# myWatch.net
KiCad netlist of a schematic drawn in EAGLE
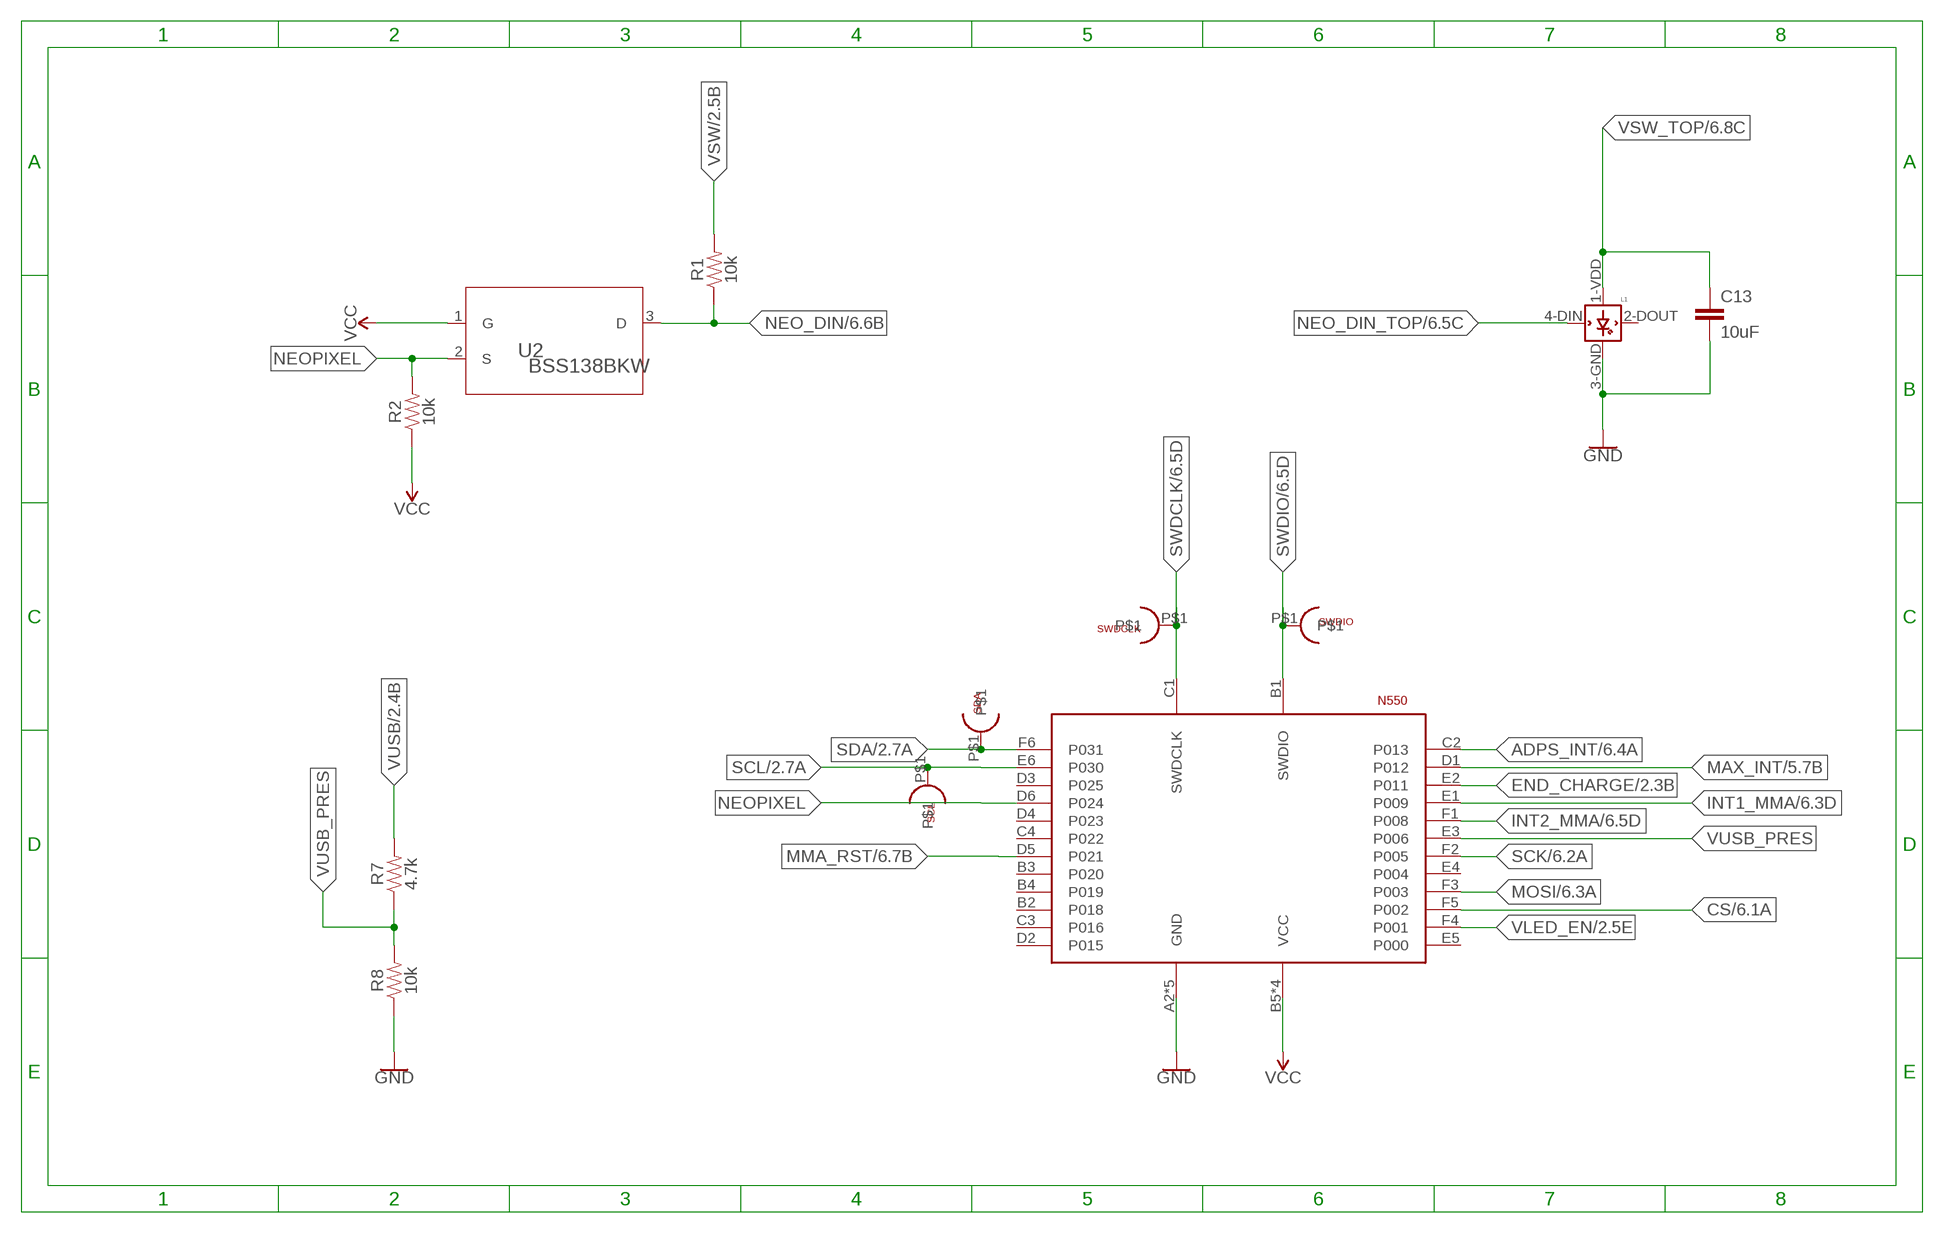
[diagram p0: schematic, sheet 1]
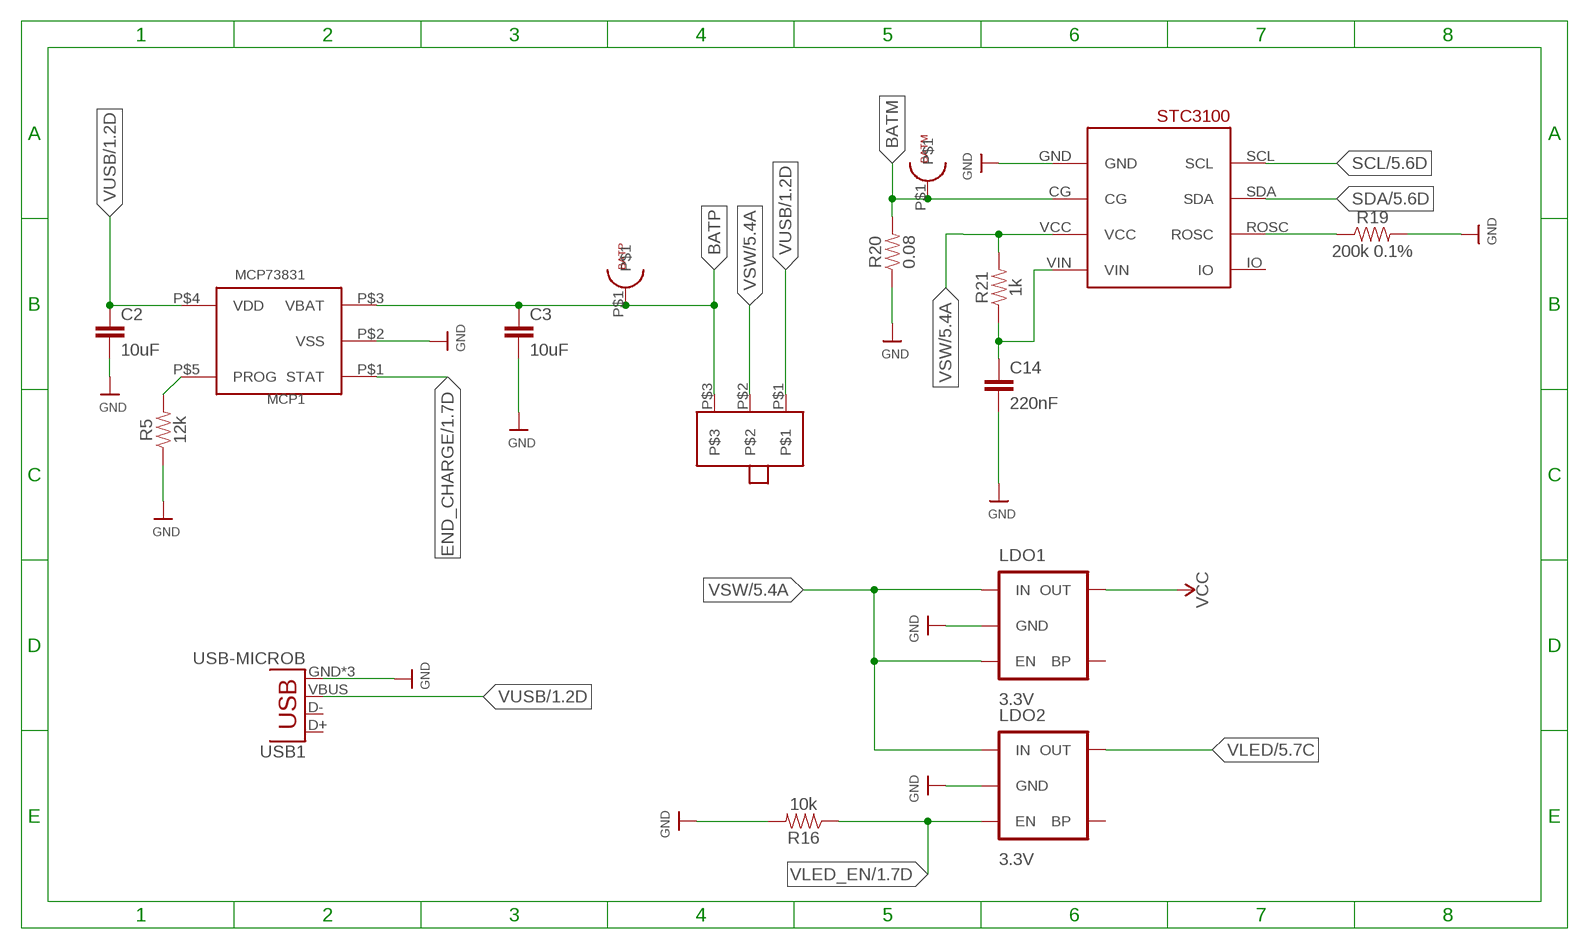
[diagram p1: schematic, sheet 2]
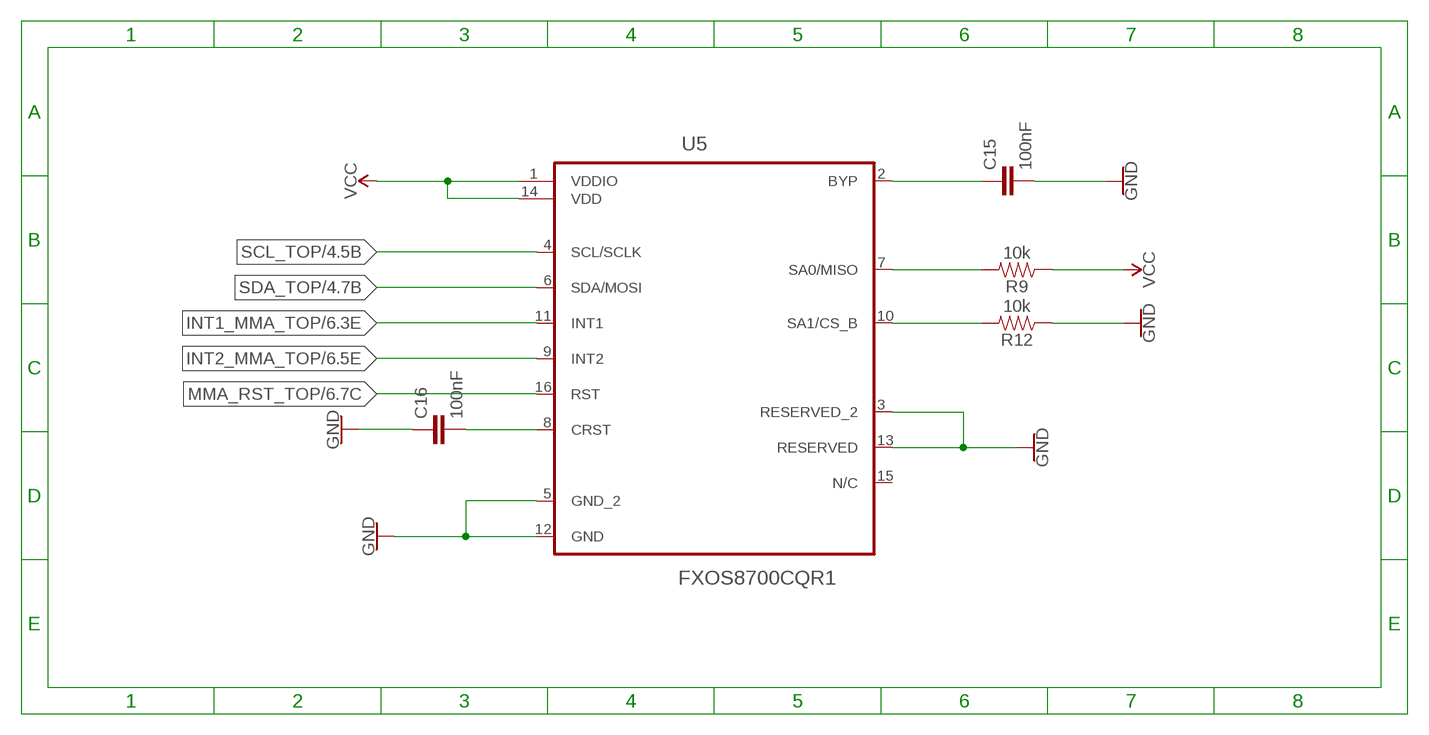
[diagram p2: schematic, sheet 3]
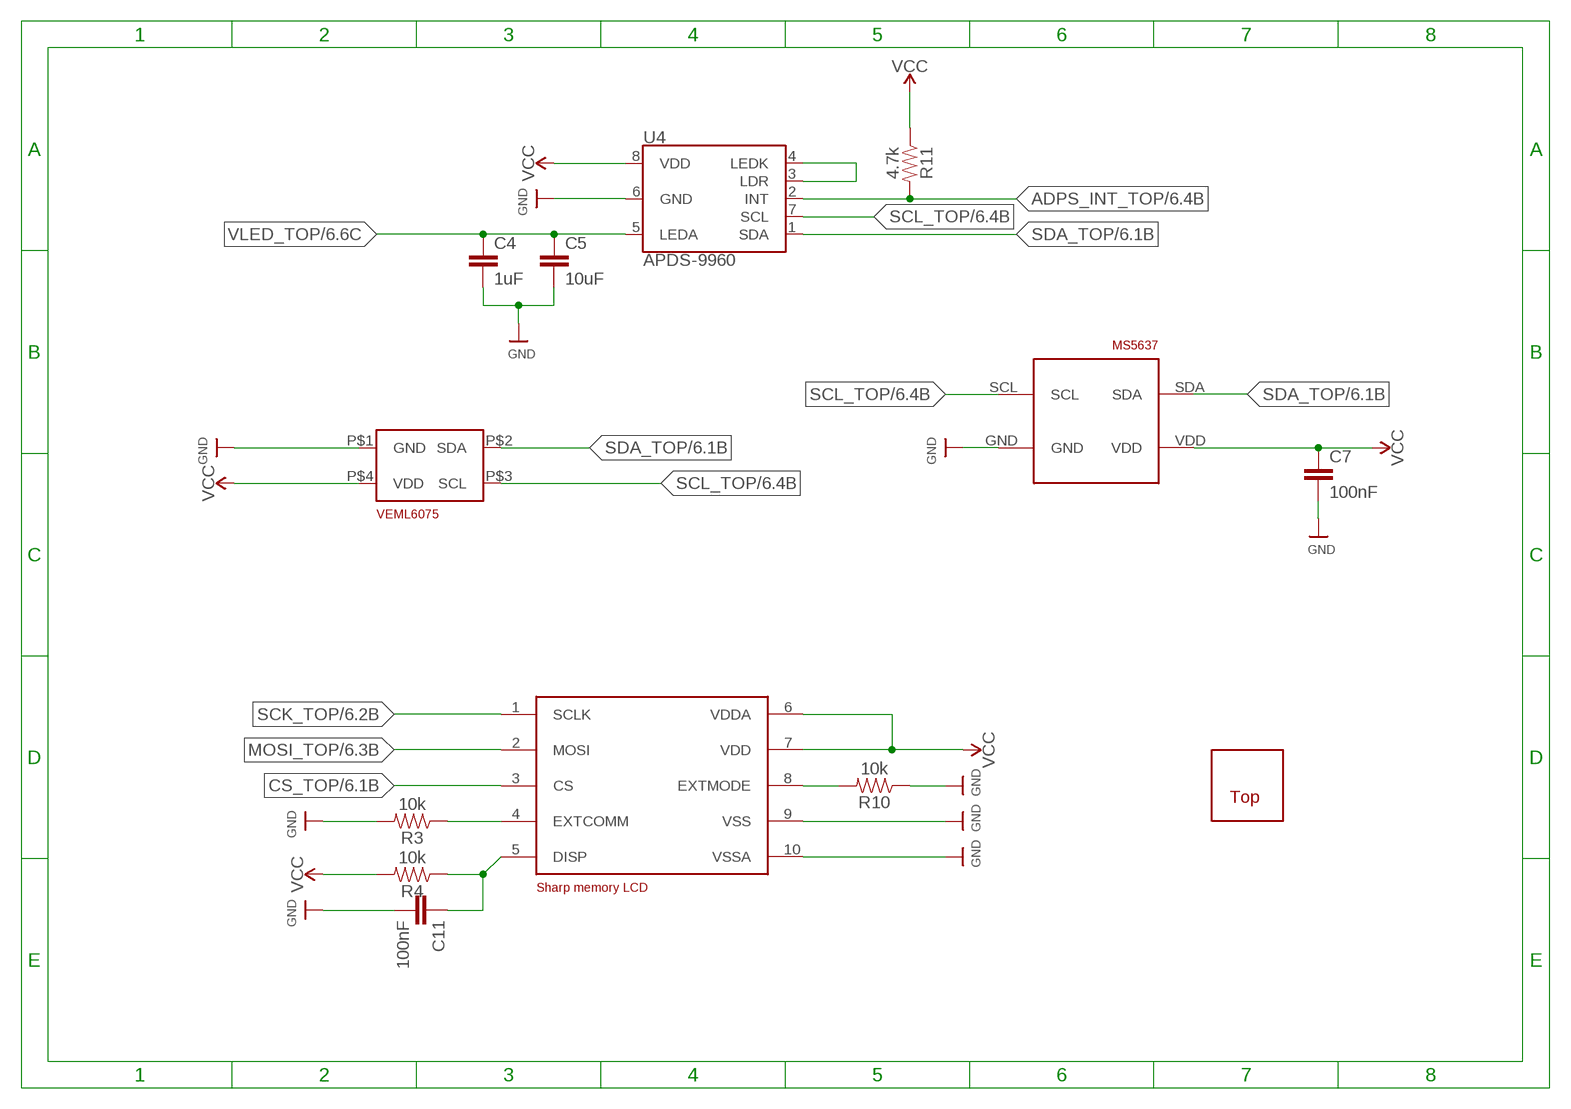
[diagram p3: schematic, sheet 4]
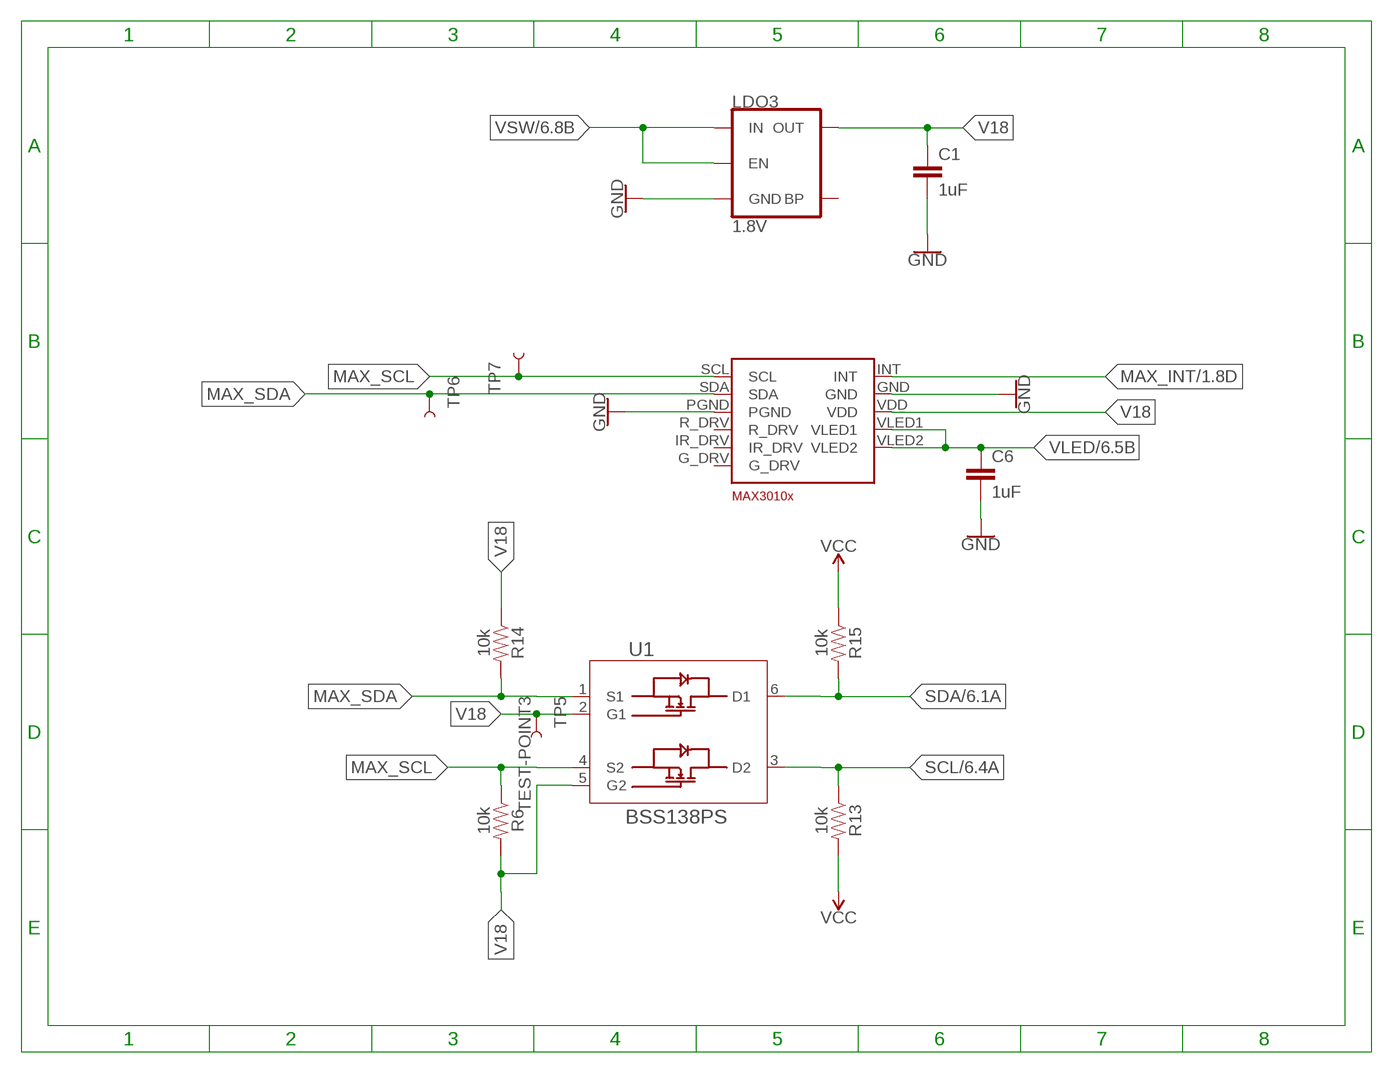
[diagram p4: schematic, sheet 5]
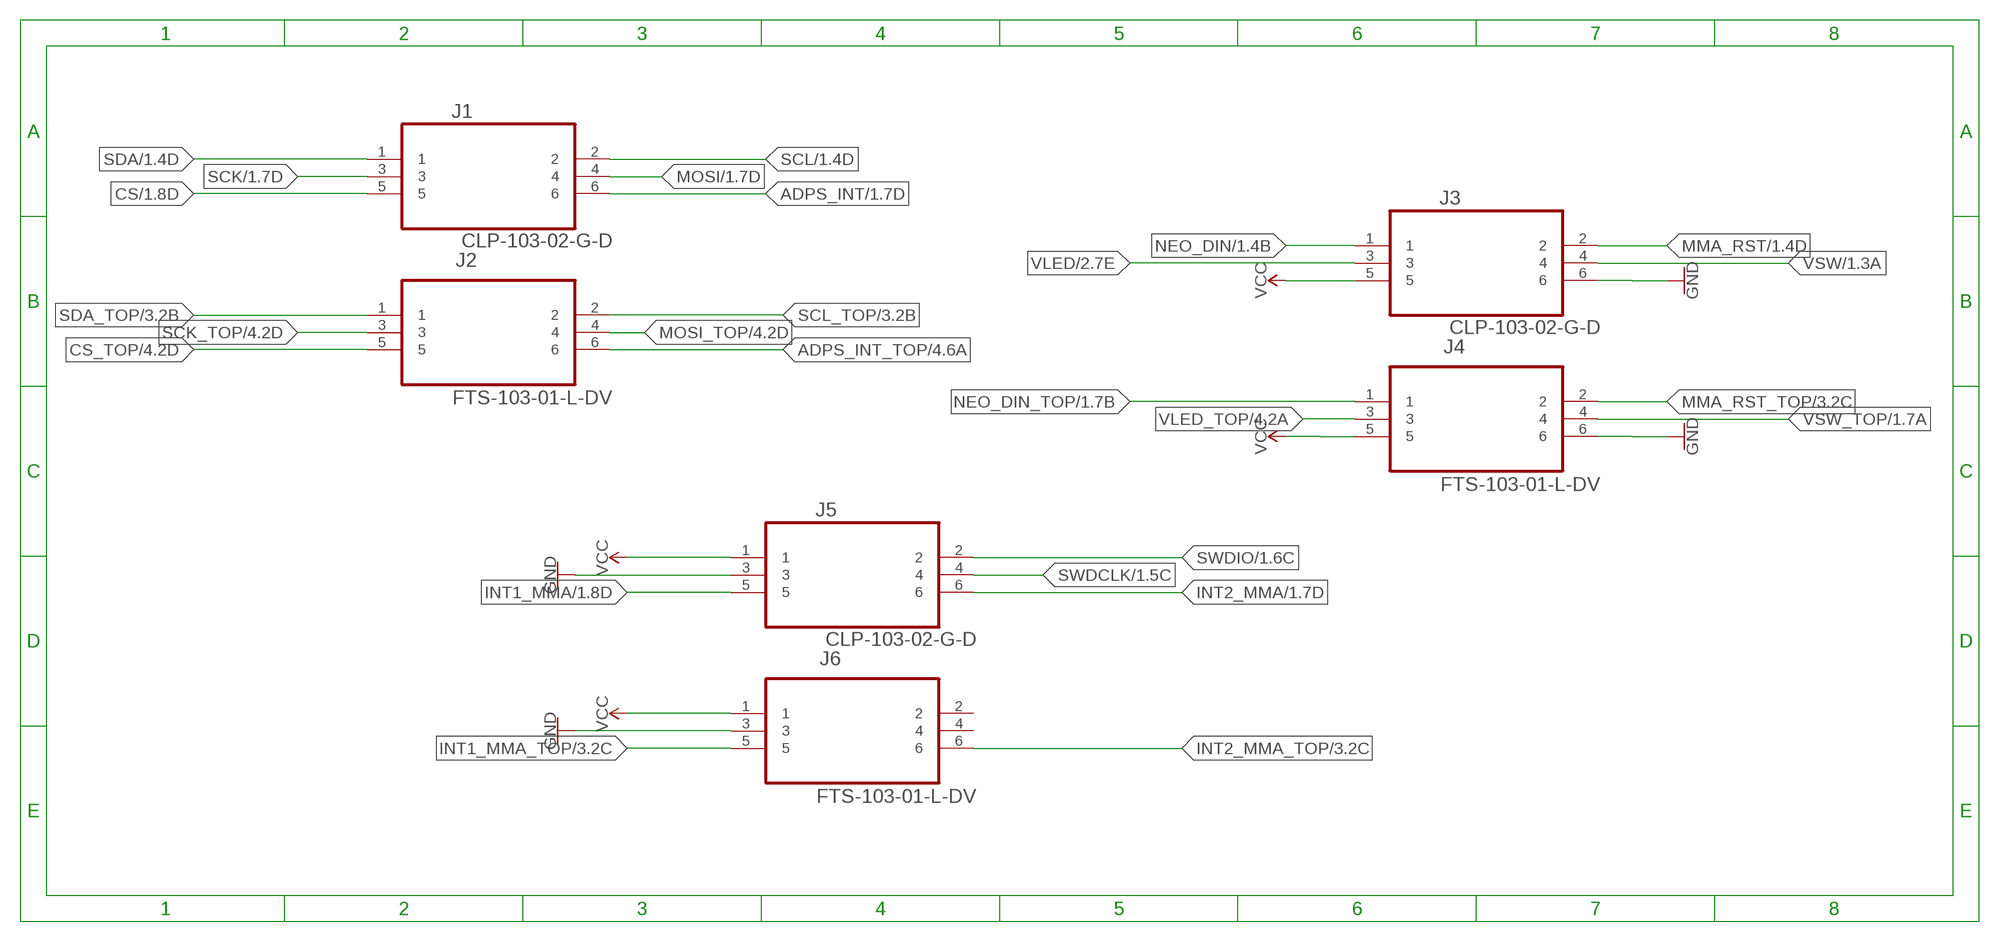
[diagram p5: schematic, sheet 6]

(export (version "E")
  (design (tool "Eeschema 10.0.6"))
  (components
    (comp (ref "C15")
      (value "100nF")
      (footprint "eagle-import:0603")
      (libsource (lib "eagle-import") (part "1.0PF-0603-50V-25%"))
    )
    (comp (ref "C16")
      (value "100nF")
      (footprint "eagle-import:0603")
      (libsource (lib "eagle-import") (part "1.0PF-0603-50V-25%"))
    )
    (comp (ref "R9")
      (value "10k")
      (footprint "eagle-import:0603")
      (libsource (lib "eagle-import") (part "0.27OHM-0603-1/10W-1%"))
    )
    (comp (ref "R12")
      (value "10k")
      (footprint "eagle-import:0603")
      (libsource (lib "eagle-import") (part "0.27OHM-0603-1/10W-1%"))
    )
    (comp (ref "U5")
      (value "FXOS8700CQR1")
      (footprint "eagle-import:QFN50P300X300X120-16N")
      (libsource (lib "eagle-import") (part "FXOS8700CQR1"))
    )
    (comp (ref "C1")
      (value "1uF")
      (footprint "eagle-import:0603")
      (libsource (lib "eagle-import") (part "5.6PF-0603-50V-5%"))
    )
    (comp (ref "C6")
      (value "1uF")
      (footprint "eagle-import:0603")
      (libsource (lib "eagle-import") (part "5.6PF-0603-50V-5%"))
    )
    (comp (ref "LDO3")
      (value "1.8V")
      (footprint "eagle-import:SOT23-5")
      (libsource (lib "eagle-import") (part "V_REG_MIC5205ADJ"))
    )
    (comp (ref "R6")
      (value "10k")
      (footprint "eagle-import:0603")
      (libsource (lib "eagle-import") (part "1.2MOHM-0603-1/10W-1%"))
    )
    (comp (ref "R13")
      (value "10k")
      (footprint "eagle-import:0603")
      (libsource (lib "eagle-import") (part "1.2MOHM-0603-1/10W-1%"))
    )
    (comp (ref "R14")
      (value "10k")
      (footprint "eagle-import:0603")
      (libsource (lib "eagle-import") (part "1.2MOHM-0603-1/10W-1%"))
    )
    (comp (ref "R15")
      (value "10k")
      (footprint "eagle-import:0603")
      (libsource (lib "eagle-import") (part "1.2MOHM-0603-1/10W-1%"))
    )
    (comp (ref "TP5")
      (value "TEST-POINT3")
      (footprint "eagle-import:PAD.03X.03")
      (libsource (lib "eagle-import") (part "TEST-POINT3"))
    )
    (comp (ref "TP6")
      (value "TEST-POINT3")
      (footprint "eagle-import:PAD.03X.03")
      (libsource (lib "eagle-import") (part "TEST-POINT3"))
    )
    (comp (ref "TP7")
      (value "TEST-POINT3")
      (footprint "eagle-import:PAD.03X.03")
      (libsource (lib "eagle-import") (part "TEST-POINT3"))
    )
    (comp (ref "U1")
      (value "BSS138PS")
      (footprint "eagle-import:SOT65P210X110-6N")
      (libsource (lib "eagle-import") (part "BSS138PS"))
    )
    (comp (ref "U3")
      (value "MAX30102")
      (footprint "eagle-import:MAX30102")
      (libsource (lib "eagle-import") (part "MAX30102"))
    )
    (comp (ref "BATM")
      (value "BATM")
      (footprint "eagle-import:TESTPOINT")
      (libsource (lib "eagle-import") (part "TESTPOINT"))
    )
    (comp (ref "BATP")
      (value "BATP")
      (footprint "eagle-import:TESTPOINT")
      (libsource (lib "eagle-import") (part "TESTPOINT"))
    )
    (comp (ref "C2")
      (value "10uF")
      (footprint "eagle-import:0603")
      (libsource (lib "eagle-import") (part "1.0PF-0603-50V-25%"))
    )
    (comp (ref "C3")
      (value "10uF")
      (footprint "eagle-import:0603")
      (libsource (lib "eagle-import") (part "1.0PF-0603-50V-25%"))
    )
    (comp (ref "C14")
      (value "220nF")
      (footprint "eagle-import:0603")
      (libsource (lib "eagle-import") (part "1.0PF-0603-50V-25%"))
    )
    (comp (ref "LDO1")
      (value "3.3V")
      (footprint "eagle-import:SOT23-5")
      (libsource (lib "eagle-import") (part "SparkFun-PowerIC_V_REG_MIC52053.3V"))
    )
    (comp (ref "LDO2")
      (value "3.3V")
      (footprint "eagle-import:SOT23-5")
      (libsource (lib "eagle-import") (part "SparkFun-PowerIC_V_REG_MIC52053.3V"))
    )
    (comp (ref "MCP1")
      (value "MCP73831")
      (footprint "eagle-import:5PIN_SOT23")
      (libsource (lib "eagle-import") (part "MCP73831"))
    )
    (comp (ref "R5")
      (value "12k")
      (footprint "eagle-import:0603")
      (libsource (lib "eagle-import") (part "0.05OHM-0603-1/5W-1%"))
    )
    (comp (ref "R16")
      (value "10k")
      (footprint "eagle-import:0603")
      (libsource (lib "eagle-import") (part "0.05OHM-0603-1/5W-1%"))
    )
    (comp (ref "R19")
      (value "200k 0.1%")
      (footprint "eagle-import:0603")
      (libsource (lib "eagle-import") (part "0.05OHM-0603-1/5W-1%"))
    )
    (comp (ref "R20")
      (value "0.08")
      (footprint "eagle-import:0603")
      (libsource (lib "eagle-import") (part "0.05OHM-0603-1/5W-1%"))
    )
    (comp (ref "R21")
      (value "1k")
      (footprint "eagle-import:0603")
      (libsource (lib "eagle-import") (part "0.05OHM-0603-1/5W-1%"))
    )
    (comp (ref "STC1")
      (value "STC3100")
      (footprint "eagle-import:STC3100")
      (libsource (lib "eagle-import") (part "STC3100"))
    )
    (comp (ref "U$10")
      (value "JS102011SAQN")
      (footprint "eagle-import:JS102011SAQN")
      (libsource (lib "eagle-import") (part "JS102011SAQN"))
    )
    (comp (ref "USB1")
      (value "USB-MICROB")
      (footprint "eagle-import:USB-MICROB")
      (libsource (lib "eagle-import") (part "USB-MICROB"))
    )
    (comp (ref "C4")
      (value "1uF")
      (footprint "eagle-import:0603")
      (libsource (lib "eagle-import") (part "1.0PF-0603-50V-25%"))
    )
    (comp (ref "C5")
      (value "10uF")
      (footprint "eagle-import:0603")
      (libsource (lib "eagle-import") (part "1.0PF-0603-50V-25%"))
    )
    (comp (ref "C7")
      (value "100nF")
      (footprint "eagle-import:0603")
      (libsource (lib "eagle-import") (part "1.5PF-0603-50V-16.667%"))
    )
    (comp (ref "C11")
      (value "100nF")
      (footprint "eagle-import:0603")
      (libsource (lib "eagle-import") (part "1.5PF-0603-50V-16.667%"))
    )
    (comp (ref "MS5637")
      (value "MS5637")
      (footprint "eagle-import:MS5637")
      (libsource (lib "eagle-import") (part "MS5637"))
    )
    (comp (ref "R3")
      (value "10k")
      (footprint "eagle-import:0603")
      (libsource (lib "eagle-import") (part "0.05OHM-0603-1/5W-1%"))
    )
    (comp (ref "R4")
      (value "10k")
      (footprint "eagle-import:0603")
      (libsource (lib "eagle-import") (part "0.05OHM-0603-1/5W-1%"))
    )
    (comp (ref "R10")
      (value "10k")
      (footprint "eagle-import:0603")
      (libsource (lib "eagle-import") (part "0.05OHM-0603-1/5W-1%"))
    )
    (comp (ref "R11")
      (value "4.7k")
      (footprint "eagle-import:0603")
      (libsource (lib "eagle-import") (part "0.05OHM-0603-1/5W-1%"))
    )
    (comp (ref "SHARP")
      (value "SHARP27")
      (footprint "eagle-import:SHARP27")
      (libsource (lib "eagle-import") (part "SHARP27"))
    )
    (comp (ref "U$2")
      (value "VEML6075")
      (footprint "eagle-import:VEML6075")
      (libsource (lib "eagle-import") (part "VEML6075"))
    )
    (comp (ref "U$6")
      (value "WATCH1")
      (footprint "eagle-import:WATCH")
      (libsource (lib "eagle-import") (part "WATCH1"))
    )
    (comp (ref "U4")
      (value "APDS-9960")
      (footprint "eagle-import:APDS-9960")
      (libsource (lib "eagle-import") (part "APDS-9960"))
    )
    (comp (ref "C13")
      (value "10uF")
      (footprint "eagle-import:0603")
      (libsource (lib "eagle-import") (part "9.0PF-0603-50V-10%"))
    )
    (comp (ref "L1")
      (value "WS2812B")
      (footprint "eagle-import:WS2812B")
      (libsource (lib "eagle-import") (part "WS2812B"))
    )
    (comp (ref "R1")
      (value "10k")
      (footprint "eagle-import:0603")
      (libsource (lib "eagle-import") (part "0.05OHM-0603-1/5W-1%"))
    )
    (comp (ref "R2")
      (value "10k")
      (footprint "eagle-import:0603")
      (libsource (lib "eagle-import") (part "0.05OHM-0603-1/5W-1%"))
    )
    (comp (ref "R7")
      (value "4.7k")
      (footprint "eagle-import:0603")
      (libsource (lib "eagle-import") (part "0.05OHM-0603-1/5W-1%"))
    )
    (comp (ref "R8")
      (value "10k")
      (footprint "eagle-import:0603")
      (libsource (lib "eagle-import") (part "0.05OHM-0603-1/5W-1%"))
    )
    (comp (ref "SCL")
      (value "SCL")
      (footprint "eagle-import:TESTPOINT")
      (libsource (lib "eagle-import") (part "TESTPOINT"))
    )
    (comp (ref "SDA")
      (value "SDA")
      (footprint "eagle-import:TESTPOINT")
      (libsource (lib "eagle-import") (part "TESTPOINT"))
    )
    (comp (ref "SWDCLK")
      (value "TESTPOINT")
      (footprint "eagle-import:TESTPOINT")
      (libsource (lib "eagle-import") (part "TESTPOINT"))
    )
    (comp (ref "SWDIO")
      (value "TESTPOINT")
      (footprint "eagle-import:TESTPOINT")
      (libsource (lib "eagle-import") (part "TESTPOINT"))
    )
    (comp (ref "U$1")
      (value "N5150")
      (footprint "eagle-import:N5150")
      (libsource (lib "eagle-import") (part "N5150"))
    )
    (comp (ref "U2")
      (value "BSS138BKW")
      (footprint "eagle-import:SOT65P210X110-3N")
      (libsource (lib "eagle-import") (part "BSS138BKW"))
    )
    (comp (ref "J1")
      (value "CLP-103-02-G-D")
      (footprint "eagle-import:SAMTEC_CLP-103-02-G-D")
      (libsource (lib "eagle-import") (part "CLP-103-02-G-D"))
    )
    (comp (ref "J2")
      (value "FTS-103-01-L-DV")
      (footprint "eagle-import:SAMTEC_FTS-103-01-L-DV")
      (libsource (lib "eagle-import") (part "FTS-103-01-L-DV"))
    )
    (comp (ref "J3")
      (value "CLP-103-02-G-D")
      (footprint "eagle-import:SAMTEC_CLP-103-02-G-D")
      (libsource (lib "eagle-import") (part "CLP-103-02-G-D"))
    )
    (comp (ref "J4")
      (value "FTS-103-01-L-DV")
      (footprint "eagle-import:SAMTEC_FTS-103-01-L-DV")
      (libsource (lib "eagle-import") (part "FTS-103-01-L-DV"))
    )
    (comp (ref "J5")
      (value "CLP-103-02-G-D")
      (footprint "eagle-import:SAMTEC_CLP-103-02-G-D")
      (libsource (lib "eagle-import") (part "CLP-103-02-G-D"))
    )
    (comp (ref "J6")
      (value "FTS-103-01-L-DV")
      (footprint "eagle-import:SAMTEC_FTS-103-01-L-DV")
      (libsource (lib "eagle-import") (part "FTS-103-01-L-DV"))
    )
  )
  (nets
    (net (code "1") (name "ADPS_INT") (class "Default")
      (node (ref "J1") (pin "6") (pinfunction "6_6") (pintype "passive"))
      (node (ref "U$1") (pin "C2") (pinfunction "P013_C2") (pintype "bidirectional"))
    )
    (net (code "2") (name "ADPS_INT_TOP") (class "Default")
      (node (ref "J2") (pin "6") (pinfunction "6_6") (pintype "passive"))
      (node (ref "R11") (pin "2") (pinfunction "2_2") (pintype "passive"))
      (node (ref "U4") (pin "2") (pinfunction "INT_2") (pintype "bidirectional"))
    )
    (net (code "3") (name "BATM") (class "Default")
      (node (ref "BATM") (pin "P$1") (pinfunction "P$1_P$1") (pintype "bidirectional"))
      (node (ref "R20") (pin "2") (pinfunction "2_2") (pintype "passive"))
      (node (ref "STC1") (pin "CG") (pinfunction "CG_CG") (pintype "bidirectional"))
    )
    (net (code "4") (name "BATP") (class "Default")
      (node (ref "BATP") (pin "P$1") (pinfunction "P$1_P$1") (pintype "bidirectional"))
      (node (ref "C3") (pin "1") (pinfunction "1_1") (pintype "passive"))
      (node (ref "MCP1") (pin "P$3") (pinfunction "VBAT_P$3") (pintype "bidirectional"))
      (node (ref "U$10") (pin "P$3") (pinfunction "P$3_P$3") (pintype "bidirectional"))
    )
    (net (code "5") (name "CS") (class "Default")
      (node (ref "J1") (pin "5") (pinfunction "5_5") (pintype "passive"))
      (node (ref "U$1") (pin "F5") (pinfunction "P002_F5") (pintype "bidirectional"))
    )
    (net (code "6") (name "CS_TOP") (class "Default")
      (node (ref "J2") (pin "5") (pinfunction "5_5") (pintype "passive"))
      (node (ref "SHARP") (pin "3") (pinfunction "CS_3") (pintype "bidirectional"))
    )
    (net (code "7") (name "END_CHARGE") (class "Default")
      (node (ref "MCP1") (pin "P$1") (pinfunction "STAT_P$1") (pintype "bidirectional"))
      (node (ref "U$1") (pin "E2") (pinfunction "P011_E2") (pintype "bidirectional"))
    )
    (net (code "8") (name "GND") (class "Default")
      (node (ref "C1") (pin "2") (pinfunction "2_2") (pintype "passive"))
      (node (ref "C11") (pin "2") (pinfunction "2_2") (pintype "passive"))
      (node (ref "C13") (pin "2") (pinfunction "2_2") (pintype "passive"))
      (node (ref "C14") (pin "2") (pinfunction "2_2") (pintype "passive"))
      (node (ref "C15") (pin "2") (pinfunction "2_2") (pintype "passive"))
      (node (ref "C16") (pin "1") (pinfunction "1_1") (pintype "passive"))
      (node (ref "C2") (pin "2") (pinfunction "2_2") (pintype "passive"))
      (node (ref "C3") (pin "2") (pinfunction "2_2") (pintype "passive"))
      (node (ref "C4") (pin "2") (pinfunction "2_2") (pintype "passive"))
      (node (ref "C5") (pin "2") (pinfunction "2_2") (pintype "passive"))
      (node (ref "C6") (pin "2") (pinfunction "2_2") (pintype "passive"))
      (node (ref "C7") (pin "2") (pinfunction "2_2") (pintype "passive"))
      (node (ref "J3") (pin "6") (pinfunction "6_6") (pintype "passive"))
      (node (ref "J4") (pin "6") (pinfunction "6_6") (pintype "passive"))
      (node (ref "J5") (pin "3") (pinfunction "3_3") (pintype "passive"))
      (node (ref "J6") (pin "3") (pinfunction "3_3") (pintype "passive"))
      (node (ref "L1") (pin "3-GND") (pinfunction "GND_3-GND") (pintype "bidirectional"))
      (node (ref "LDO1") (pin "2") (pinfunction "GND_2") (pintype "input"))
      (node (ref "LDO2") (pin "2") (pinfunction "GND_2") (pintype "input"))
      (node (ref "LDO3") (pin "2") (pinfunction "GND_2") (pintype "input"))
      (node (ref "MCP1") (pin "P$2") (pinfunction "VSS_P$2") (pintype "bidirectional"))
      (node (ref "MS5637") (pin "GND") (pinfunction "GND_GND") (pintype "bidirectional"))
      (node (ref "R10") (pin "1") (pinfunction "1_1") (pintype "passive"))
      (node (ref "R12") (pin "1") (pinfunction "1_1") (pintype "passive"))
      (node (ref "R16") (pin "2") (pinfunction "2_2") (pintype "passive"))
      (node (ref "R19") (pin "2") (pinfunction "2_2") (pintype "passive"))
      (node (ref "R20") (pin "1") (pinfunction "1_1") (pintype "passive"))
      (node (ref "R3") (pin "2") (pinfunction "2_2") (pintype "passive"))
      (node (ref "R5") (pin "1") (pinfunction "1_1") (pintype "passive"))
      (node (ref "R8") (pin "1") (pinfunction "1_1") (pintype "passive"))
      (node (ref "SHARP") (pin "10") (pinfunction "VSSA_10") (pintype "bidirectional"))
      (node (ref "SHARP") (pin "9") (pinfunction "VSS_9") (pintype "bidirectional"))
      (node (ref "STC1") (pin "GND") (pinfunction "GND_GND") (pintype "bidirectional"))
      (node (ref "U$1") (pin "A2") (pinfunction "GND_A2") (pintype "bidirectional"))
      (node (ref "U$1") (pin "A3") (pinfunction "GND_A3") (pintype "bidirectional"))
      (node (ref "U$1") (pin "A4") (pinfunction "GND_A4") (pintype "bidirectional"))
      (node (ref "U$1") (pin "A5") (pinfunction "GND_A5") (pintype "bidirectional"))
      (node (ref "U$1") (pin "A6") (pinfunction "GND_A6") (pintype "bidirectional"))
      (node (ref "U$2") (pin "P$1") (pinfunction "GND_P$1") (pintype "bidirectional"))
      (node (ref "U3") (pin "GND") (pinfunction "GND_GND") (pintype "bidirectional"))
      (node (ref "U3") (pin "PGND") (pinfunction "PGND_PGND") (pintype "bidirectional"))
      (node (ref "U4") (pin "6") (pinfunction "GND_6") (pintype "bidirectional"))
      (node (ref "U5") (pin "12") (pinfunction "GND_12") (pintype "passive"))
      (node (ref "U5") (pin "13") (pinfunction "RESERVED_13") (pintype "passive"))
      (node (ref "U5") (pin "3") (pinfunction "RESERVED_2_3") (pintype "passive"))
      (node (ref "U5") (pin "5") (pinfunction "GND_2_5") (pintype "passive"))
      (node (ref "USB1") (pin "GND") (pinfunction "GND_GND") (pintype "bidirectional"))
      (node (ref "USB1") (pin "MT1") (pinfunction "GND_MT1") (pintype "bidirectional"))
      (node (ref "USB1") (pin "MT2") (pinfunction "GND_MT2") (pintype "bidirectional"))
    )
    (net (code "9") (name "INT1_MMA") (class "Default")
      (node (ref "J5") (pin "5") (pinfunction "5_5") (pintype "passive"))
      (node (ref "U$1") (pin "E1") (pinfunction "P009_E1") (pintype "bidirectional"))
    )
    (net (code "10") (name "INT1_MMA_TOP") (class "Default")
      (node (ref "J6") (pin "5") (pinfunction "5_5") (pintype "passive"))
      (node (ref "U5") (pin "11") (pinfunction "INT1_11") (pintype "input"))
    )
    (net (code "11") (name "INT2_MMA") (class "Default")
      (node (ref "J5") (pin "6") (pinfunction "6_6") (pintype "passive"))
      (node (ref "U$1") (pin "F1") (pinfunction "P008_F1") (pintype "bidirectional"))
    )
    (net (code "12") (name "INT2_MMA_TOP") (class "Default")
      (node (ref "J6") (pin "6") (pinfunction "6_6") (pintype "passive"))
      (node (ref "U5") (pin "9") (pinfunction "INT2_9") (pintype "input"))
    )
    (net (code "13") (name "MAX_INT") (class "Default")
      (node (ref "U$1") (pin "D1") (pinfunction "P012_D1") (pintype "bidirectional"))
      (node (ref "U3") (pin "INT") (pinfunction "INT_INT") (pintype "bidirectional"))
    )
    (net (code "14") (name "MAX_SCL") (class "Default")
      (node (ref "R6") (pin "1") (pinfunction "1_1") (pintype "passive"))
      (node (ref "TP7") (pin "P$1") (pinfunction "1_P$1") (pintype "bidirectional"))
      (node (ref "U1") (pin "4") (pinfunction "S2_4") (pintype "output"))
      (node (ref "U3") (pin "SCL") (pinfunction "SCL_SCL") (pintype "bidirectional"))
    )
    (net (code "15") (name "MAX_SDA") (class "Default")
      (node (ref "R14") (pin "2") (pinfunction "2_2") (pintype "passive"))
      (node (ref "TP6") (pin "P$1") (pinfunction "1_P$1") (pintype "bidirectional"))
      (node (ref "U1") (pin "1") (pinfunction "S1_1") (pintype "output"))
      (node (ref "U3") (pin "SDA") (pinfunction "SDA_SDA") (pintype "bidirectional"))
    )
    (net (code "16") (name "MMA_RST") (class "Default")
      (node (ref "J3") (pin "2") (pinfunction "2_2") (pintype "passive"))
      (node (ref "U$1") (pin "D5") (pinfunction "P021_D5") (pintype "bidirectional"))
    )
    (net (code "17") (name "MMA_RST_TOP") (class "Default")
      (node (ref "J4") (pin "2") (pinfunction "2_2") (pintype "passive"))
      (node (ref "U5") (pin "16") (pinfunction "RST_16") (pintype "input"))
    )
    (net (code "18") (name "MOSI") (class "Default")
      (node (ref "J1") (pin "4") (pinfunction "4_4") (pintype "passive"))
      (node (ref "U$1") (pin "F3") (pinfunction "P003_F3") (pintype "bidirectional"))
    )
    (net (code "19") (name "MOSI_TOP") (class "Default")
      (node (ref "J2") (pin "4") (pinfunction "4_4") (pintype "passive"))
      (node (ref "SHARP") (pin "2") (pinfunction "MOSI_2") (pintype "bidirectional"))
    )
    (net (code "20") (name "NEOPIXEL") (class "Default")
      (node (ref "R2") (pin "2") (pinfunction "2_2") (pintype "passive"))
      (node (ref "U$1") (pin "D6") (pinfunction "P024_D6") (pintype "bidirectional"))
      (node (ref "U2") (pin "2") (pinfunction "S_2") (pintype "passive"))
    )
    (net (code "21") (name "NEO_DIN") (class "Default")
      (node (ref "J3") (pin "1") (pinfunction "1_1") (pintype "passive"))
      (node (ref "R1") (pin "1") (pinfunction "1_1") (pintype "passive"))
      (node (ref "U2") (pin "3") (pinfunction "D_3") (pintype "passive"))
    )
    (net (code "22") (name "NEO_DIN_TOP") (class "Default")
      (node (ref "J4") (pin "1") (pinfunction "1_1") (pintype "passive"))
      (node (ref "L1") (pin "4-DIN") (pinfunction "DIN_4-DIN") (pintype "input"))
    )
    (net (code "23") (name "Net-(C14-Pad1)") (class "Default")
      (node (ref "C14") (pin "1") (pinfunction "1_1") (pintype "passive"))
      (node (ref "R21") (pin "1") (pinfunction "1_1") (pintype "passive"))
      (node (ref "STC1") (pin "VIN") (pinfunction "VIN_VIN") (pintype "bidirectional"))
    )
    (net (code "24") (name "Net-(MCP1-PROG)") (class "Default")
      (node (ref "MCP1") (pin "P$5") (pinfunction "PROG_P$5") (pintype "bidirectional"))
      (node (ref "R5") (pin "2") (pinfunction "2_2") (pintype "passive"))
    )
    (net (code "25") (name "Net-(R19-Pad1)") (class "Default")
      (node (ref "R19") (pin "1") (pinfunction "1_1") (pintype "passive"))
      (node (ref "STC1") (pin "ROSC") (pinfunction "ROSC_ROSC") (pintype "bidirectional"))
    )
    (net (code "26") (name "Net-(SHARP-DISP)") (class "Default")
      (node (ref "C11") (pin "1") (pinfunction "1_1") (pintype "passive"))
      (node (ref "R4") (pin "1") (pinfunction "1_1") (pintype "passive"))
      (node (ref "SHARP") (pin "5") (pinfunction "DISP_5") (pintype "bidirectional"))
    )
    (net (code "27") (name "Net-(SHARP-EXTCOMM)") (class "Default")
      (node (ref "R3") (pin "1") (pinfunction "1_1") (pintype "passive"))
      (node (ref "SHARP") (pin "4") (pinfunction "EXTCOMM_4") (pintype "bidirectional"))
    )
    (net (code "28") (name "Net-(SHARP-EXTMODE)") (class "Default")
      (node (ref "R10") (pin "2") (pinfunction "2_2") (pintype "passive"))
      (node (ref "SHARP") (pin "8") (pinfunction "EXTMODE_8") (pintype "bidirectional"))
    )
    (net (code "29") (name "Net-(U4-LDR)") (class "Default")
      (node (ref "U4") (pin "3") (pinfunction "LDR_3") (pintype "bidirectional"))
      (node (ref "U4") (pin "4") (pinfunction "LEDK_4") (pintype "bidirectional"))
    )
    (net (code "30") (name "Net-(U5-BYP)") (class "Default")
      (node (ref "C15") (pin "1") (pinfunction "1_1") (pintype "passive"))
      (node (ref "U5") (pin "2") (pinfunction "BYP_2") (pintype "passive"))
    )
    (net (code "31") (name "Net-(U5-CRST)") (class "Default")
      (node (ref "C16") (pin "2") (pinfunction "2_2") (pintype "passive"))
      (node (ref "U5") (pin "8") (pinfunction "CRST_8") (pintype "passive"))
    )
    (net (code "32") (name "Net-(U5-SA0{slash}MISO)") (class "Default")
      (node (ref "R9") (pin "2") (pinfunction "2_2") (pintype "passive"))
      (node (ref "U5") (pin "7") (pinfunction "SA0/MISO_7") (pintype "bidirectional"))
    )
    (net (code "33") (name "Net-(U5-SA1{slash}CS_B)") (class "Default")
      (node (ref "R12") (pin "2") (pinfunction "2_2") (pintype "passive"))
      (node (ref "U5") (pin "10") (pinfunction "SA1/CS_B_10") (pintype "input"))
    )
    (net (code "34") (name "SCK") (class "Default")
      (node (ref "J1") (pin "3") (pinfunction "3_3") (pintype "passive"))
      (node (ref "U$1") (pin "F2") (pinfunction "P005_F2") (pintype "bidirectional"))
    )
    (net (code "35") (name "SCK_TOP") (class "Default")
      (node (ref "J2") (pin "3") (pinfunction "3_3") (pintype "passive"))
      (node (ref "SHARP") (pin "1") (pinfunction "SCLK_1") (pintype "bidirectional"))
    )
    (net (code "36") (name "SCL") (class "Default")
      (node (ref "J1") (pin "2") (pinfunction "2_2") (pintype "passive"))
      (node (ref "R13") (pin "1") (pinfunction "1_1") (pintype "passive"))
      (node (ref "SCL") (pin "P$1") (pinfunction "P$1_P$1") (pintype "bidirectional"))
      (node (ref "STC1") (pin "SCL") (pinfunction "SCL_SCL") (pintype "bidirectional"))
      (node (ref "U$1") (pin "E6") (pinfunction "P030_E6") (pintype "bidirectional"))
      (node (ref "U1") (pin "3") (pinfunction "D2_3") (pintype "input"))
    )
    (net (code "37") (name "SCL_TOP") (class "Default")
      (node (ref "J2") (pin "2") (pinfunction "2_2") (pintype "passive"))
      (node (ref "MS5637") (pin "SCL") (pinfunction "SCL_SCL") (pintype "bidirectional"))
      (node (ref "U$2") (pin "P$3") (pinfunction "SCL_P$3") (pintype "bidirectional"))
      (node (ref "U4") (pin "7") (pinfunction "SCL_7") (pintype "bidirectional"))
      (node (ref "U5") (pin "4") (pinfunction "SCL/SCLK_4") (pintype "input"))
    )
    (net (code "38") (name "SDA") (class "Default")
      (node (ref "J1") (pin "1") (pinfunction "1_1") (pintype "passive"))
      (node (ref "R15") (pin "2") (pinfunction "2_2") (pintype "passive"))
      (node (ref "SDA") (pin "P$1") (pinfunction "P$1_P$1") (pintype "bidirectional"))
      (node (ref "STC1") (pin "SDA") (pinfunction "SDA_SDA") (pintype "bidirectional"))
      (node (ref "U$1") (pin "F6") (pinfunction "P031_F6") (pintype "bidirectional"))
      (node (ref "U1") (pin "6") (pinfunction "D1_6") (pintype "input"))
    )
    (net (code "39") (name "SDA_TOP") (class "Default")
      (node (ref "J2") (pin "1") (pinfunction "1_1") (pintype "passive"))
      (node (ref "MS5637") (pin "SDA") (pinfunction "SDA_SDA") (pintype "bidirectional"))
      (node (ref "U$2") (pin "P$2") (pinfunction "SDA_P$2") (pintype "bidirectional"))
      (node (ref "U4") (pin "1") (pinfunction "SDA_1") (pintype "bidirectional"))
      (node (ref "U5") (pin "6") (pinfunction "SDA/MOSI_6") (pintype "bidirectional"))
    )
    (net (code "40") (name "SWDCLK") (class "Default")
      (node (ref "J5") (pin "4") (pinfunction "4_4") (pintype "passive"))
      (node (ref "SWDCLK") (pin "P$1") (pinfunction "P$1_P$1") (pintype "bidirectional"))
      (node (ref "U$1") (pin "C1") (pinfunction "SWDCLK_C1") (pintype "bidirectional"))
    )
    (net (code "41") (name "SWDIO") (class "Default")
      (node (ref "J5") (pin "2") (pinfunction "2_2") (pintype "passive"))
      (node (ref "SWDIO") (pin "P$1") (pinfunction "P$1_P$1") (pintype "bidirectional"))
      (node (ref "U$1") (pin "B1") (pinfunction "SWDIO_B1") (pintype "bidirectional"))
    )
    (net (code "42") (name "V18") (class "Default")
      (node (ref "C1") (pin "1") (pinfunction "1_1") (pintype "passive"))
      (node (ref "LDO3") (pin "5") (pinfunction "OUT_5") (pintype "passive"))
      (node (ref "R14") (pin "1") (pinfunction "1_1") (pintype "passive"))
      (node (ref "R6") (pin "2") (pinfunction "2_2") (pintype "passive"))
      (node (ref "TP5") (pin "P$1") (pinfunction "1_P$1") (pintype "bidirectional"))
      (node (ref "U1") (pin "2") (pinfunction "G1_2") (pintype "input"))
      (node (ref "U1") (pin "5") (pinfunction "G2_5") (pintype "input"))
      (node (ref "U3") (pin "VDD") (pinfunction "VDD_VDD") (pintype "bidirectional"))
    )
    (net (code "43") (name "VCC") (class "Default")
      (node (ref "C7") (pin "1") (pinfunction "1_1") (pintype "passive"))
      (node (ref "J3") (pin "5") (pinfunction "5_5") (pintype "passive"))
      (node (ref "J4") (pin "5") (pinfunction "5_5") (pintype "passive"))
      (node (ref "J5") (pin "1") (pinfunction "1_1") (pintype "passive"))
      (node (ref "J6") (pin "1") (pinfunction "1_1") (pintype "passive"))
      (node (ref "LDO1") (pin "5") (pinfunction "OUT_5") (pintype "passive"))
      (node (ref "MS5637") (pin "VDD") (pinfunction "VDD_VDD") (pintype "bidirectional"))
      (node (ref "R11") (pin "1") (pinfunction "1_1") (pintype "passive"))
      (node (ref "R13") (pin "2") (pinfunction "2_2") (pintype "passive"))
      (node (ref "R15") (pin "1") (pinfunction "1_1") (pintype "passive"))
      (node (ref "R2") (pin "1") (pinfunction "1_1") (pintype "passive"))
      (node (ref "R4") (pin "2") (pinfunction "2_2") (pintype "passive"))
      (node (ref "R9") (pin "1") (pinfunction "1_1") (pintype "passive"))
      (node (ref "SHARP") (pin "6") (pinfunction "VDDA_6") (pintype "bidirectional"))
      (node (ref "SHARP") (pin "7") (pinfunction "VDD_7") (pintype "bidirectional"))
      (node (ref "U$1") (pin "B5") (pinfunction "VCC_B5") (pintype "bidirectional"))
      (node (ref "U$1") (pin "B6") (pinfunction "VCC_B6") (pintype "bidirectional"))
      (node (ref "U$1") (pin "C5") (pinfunction "VCC_C5") (pintype "bidirectional"))
      (node (ref "U$1") (pin "C6") (pinfunction "VCC_C6") (pintype "bidirectional"))
      (node (ref "U$2") (pin "P$4") (pinfunction "VDD_P$4") (pintype "bidirectional"))
      (node (ref "U2") (pin "1") (pinfunction "G_1") (pintype "passive"))
      (node (ref "U4") (pin "8") (pinfunction "VDD_8") (pintype "bidirectional"))
      (node (ref "U5") (pin "1") (pinfunction "VDDIO_1") (pintype "power_in"))
      (node (ref "U5") (pin "14") (pinfunction "VDD_14") (pintype "power_in"))
    )
    (net (code "44") (name "VLED") (class "Default")
      (node (ref "C6") (pin "1") (pinfunction "1_1") (pintype "passive"))
      (node (ref "J3") (pin "3") (pinfunction "3_3") (pintype "passive"))
      (node (ref "LDO2") (pin "5") (pinfunction "OUT_5") (pintype "passive"))
      (node (ref "U3") (pin "VLED1") (pinfunction "VLED1_VLED1") (pintype "bidirectional"))
      (node (ref "U3") (pin "VLED2") (pinfunction "VLED2_VLED2") (pintype "bidirectional"))
    )
    (net (code "45") (name "VLED_EN") (class "Default")
      (node (ref "LDO2") (pin "3") (pinfunction "EN_3") (pintype "input"))
      (node (ref "R16") (pin "1") (pinfunction "1_1") (pintype "passive"))
      (node (ref "U$1") (pin "F4") (pinfunction "P001_F4") (pintype "bidirectional"))
    )
    (net (code "46") (name "VLED_TOP") (class "Default")
      (node (ref "C4") (pin "1") (pinfunction "1_1") (pintype "passive"))
      (node (ref "C5") (pin "1") (pinfunction "1_1") (pintype "passive"))
      (node (ref "J4") (pin "3") (pinfunction "3_3") (pintype "passive"))
      (node (ref "U4") (pin "5") (pinfunction "LEDA_5") (pintype "bidirectional"))
    )
    (net (code "47") (name "VSW") (class "Default")
      (node (ref "J3") (pin "4") (pinfunction "4_4") (pintype "passive"))
      (node (ref "LDO1") (pin "1") (pinfunction "IN_1") (pintype "input"))
      (node (ref "LDO1") (pin "3") (pinfunction "EN_3") (pintype "input"))
      (node (ref "LDO2") (pin "1") (pinfunction "IN_1") (pintype "input"))
      (node (ref "LDO3") (pin "1") (pinfunction "IN_1") (pintype "input"))
      (node (ref "LDO3") (pin "3") (pinfunction "EN_3") (pintype "input"))
      (node (ref "R1") (pin "2") (pinfunction "2_2") (pintype "passive"))
      (node (ref "R21") (pin "2") (pinfunction "2_2") (pintype "passive"))
      (node (ref "STC1") (pin "VCC") (pinfunction "VCC_VCC") (pintype "bidirectional"))
      (node (ref "U$10") (pin "P$2") (pinfunction "P$2_P$2") (pintype "bidirectional"))
    )
    (net (code "48") (name "VSW_TOP") (class "Default")
      (node (ref "C13") (pin "1") (pinfunction "1_1") (pintype "passive"))
      (node (ref "J4") (pin "4") (pinfunction "4_4") (pintype "passive"))
      (node (ref "L1") (pin "1-VDD") (pinfunction "VDD_1-VDD") (pintype "bidirectional"))
    )
    (net (code "49") (name "VUSB") (class "Default")
      (node (ref "C2") (pin "1") (pinfunction "1_1") (pintype "passive"))
      (node (ref "MCP1") (pin "P$4") (pinfunction "VDD_P$4") (pintype "bidirectional"))
      (node (ref "R7") (pin "2") (pinfunction "2_2") (pintype "passive"))
      (node (ref "U$10") (pin "P$1") (pinfunction "P$1_P$1") (pintype "bidirectional"))
      (node (ref "USB1") (pin "VBUS") (pinfunction "VBUS_VBUS") (pintype "bidirectional"))
    )
    (net (code "50") (name "VUSB_PRES") (class "Default")
      (node (ref "R7") (pin "1") (pinfunction "1_1") (pintype "passive"))
      (node (ref "R8") (pin "2") (pinfunction "2_2") (pintype "passive"))
      (node (ref "U$1") (pin "E3") (pinfunction "P006_E3") (pintype "bidirectional"))
    )
    (net (code "51") (name "unconnected-(J6-Pad2)") (class "Default")
      (node (ref "J6") (pin "2") (pinfunction "2_2") (pintype "passive"))
    )
    (net (code "52") (name "unconnected-(J6-Pad4)") (class "Default")
      (node (ref "J6") (pin "4") (pinfunction "4_4") (pintype "passive"))
    )
    (net (code "53") (name "unconnected-(L1-DOUT-Pad2-DOUT)") (class "Default")
      (node (ref "L1") (pin "2-DOUT") (pinfunction "DOUT_2-DOUT") (pintype "output"))
    )
    (net (code "54") (name "unconnected-(LDO1-BP-Pad4)") (class "Default")
      (node (ref "LDO1") (pin "4") (pinfunction "BP_4") (pintype "input"))
    )
    (net (code "55") (name "unconnected-(LDO2-BP-Pad4)") (class "Default")
      (node (ref "LDO2") (pin "4") (pinfunction "BP_4") (pintype "input"))
    )
    (net (code "56") (name "unconnected-(LDO3-BP-Pad4)") (class "Default")
      (node (ref "LDO3") (pin "4") (pinfunction "BP_4") (pintype "input"))
    )
    (net (code "57") (name "unconnected-(STC1-PadIO)") (class "Default")
      (node (ref "STC1") (pin "IO") (pinfunction "IO_IO") (pintype "bidirectional"))
    )
    (net (code "58") (name "unconnected-(U$1-P000-PadE5)") (class "Default")
      (node (ref "U$1") (pin "E5") (pinfunction "P000_E5") (pintype "bidirectional"))
    )
    (net (code "59") (name "unconnected-(U$1-P004-PadE4)") (class "Default")
      (node (ref "U$1") (pin "E4") (pinfunction "P004_E4") (pintype "bidirectional"))
    )
    (net (code "60") (name "unconnected-(U$1-P015-PadD2)") (class "Default")
      (node (ref "U$1") (pin "D2") (pinfunction "P015_D2") (pintype "bidirectional"))
    )
    (net (code "61") (name "unconnected-(U$1-P016-PadC3)") (class "Default")
      (node (ref "U$1") (pin "C3") (pinfunction "P016_C3") (pintype "bidirectional"))
    )
    (net (code "62") (name "unconnected-(U$1-P018-PadB2)") (class "Default")
      (node (ref "U$1") (pin "B2") (pinfunction "P018_B2") (pintype "bidirectional"))
    )
    (net (code "63") (name "unconnected-(U$1-P019-PadB4)") (class "Default")
      (node (ref "U$1") (pin "B4") (pinfunction "P019_B4") (pintype "bidirectional"))
    )
    (net (code "64") (name "unconnected-(U$1-P020-PadB3)") (class "Default")
      (node (ref "U$1") (pin "B3") (pinfunction "P020_B3") (pintype "bidirectional"))
    )
    (net (code "65") (name "unconnected-(U$1-P022-PadC4)") (class "Default")
      (node (ref "U$1") (pin "C4") (pinfunction "P022_C4") (pintype "bidirectional"))
    )
    (net (code "66") (name "unconnected-(U$1-P023-PadD4)") (class "Default")
      (node (ref "U$1") (pin "D4") (pinfunction "P023_D4") (pintype "bidirectional"))
    )
    (net (code "67") (name "unconnected-(U$1-P025-PadD3)") (class "Default")
      (node (ref "U$1") (pin "D3") (pinfunction "P025_D3") (pintype "bidirectional"))
    )
    (net (code "68") (name "unconnected-(U3-PadG_DRV)") (class "Default")
      (node (ref "U3") (pin "G_DRV") (pinfunction "G_DRV_G_DRV") (pintype "bidirectional"))
    )
    (net (code "69") (name "unconnected-(U3-PadIR_DRV)") (class "Default")
      (node (ref "U3") (pin "IR_DRV") (pinfunction "IR_DRV_IR_DRV") (pintype "bidirectional"))
    )
    (net (code "70") (name "unconnected-(U3-PadR_DRV)") (class "Default")
      (node (ref "U3") (pin "R_DRV") (pinfunction "R_DRV_R_DRV") (pintype "bidirectional"))
    )
    (net (code "71") (name "unconnected-(U5-N{slash}C-Pad15)") (class "Default")
      (node (ref "U5") (pin "15") (pinfunction "N/C_15") (pintype "no_connect"))
    )
    (net (code "72") (name "unconnected-(USB1-PadD+)") (class "Default")
      (node (ref "USB1") (pin "D+") (pinfunction "D+_D+") (pintype "bidirectional"))
    )
    (net (code "73") (name "unconnected-(USB1-PadD-)") (class "Default")
      (node (ref "USB1") (pin "D-") (pinfunction "D-_D-") (pintype "bidirectional"))
    )
  )
)
